# MiniCar.net
KiCad netlist of a schematic drawn in Altium Designer
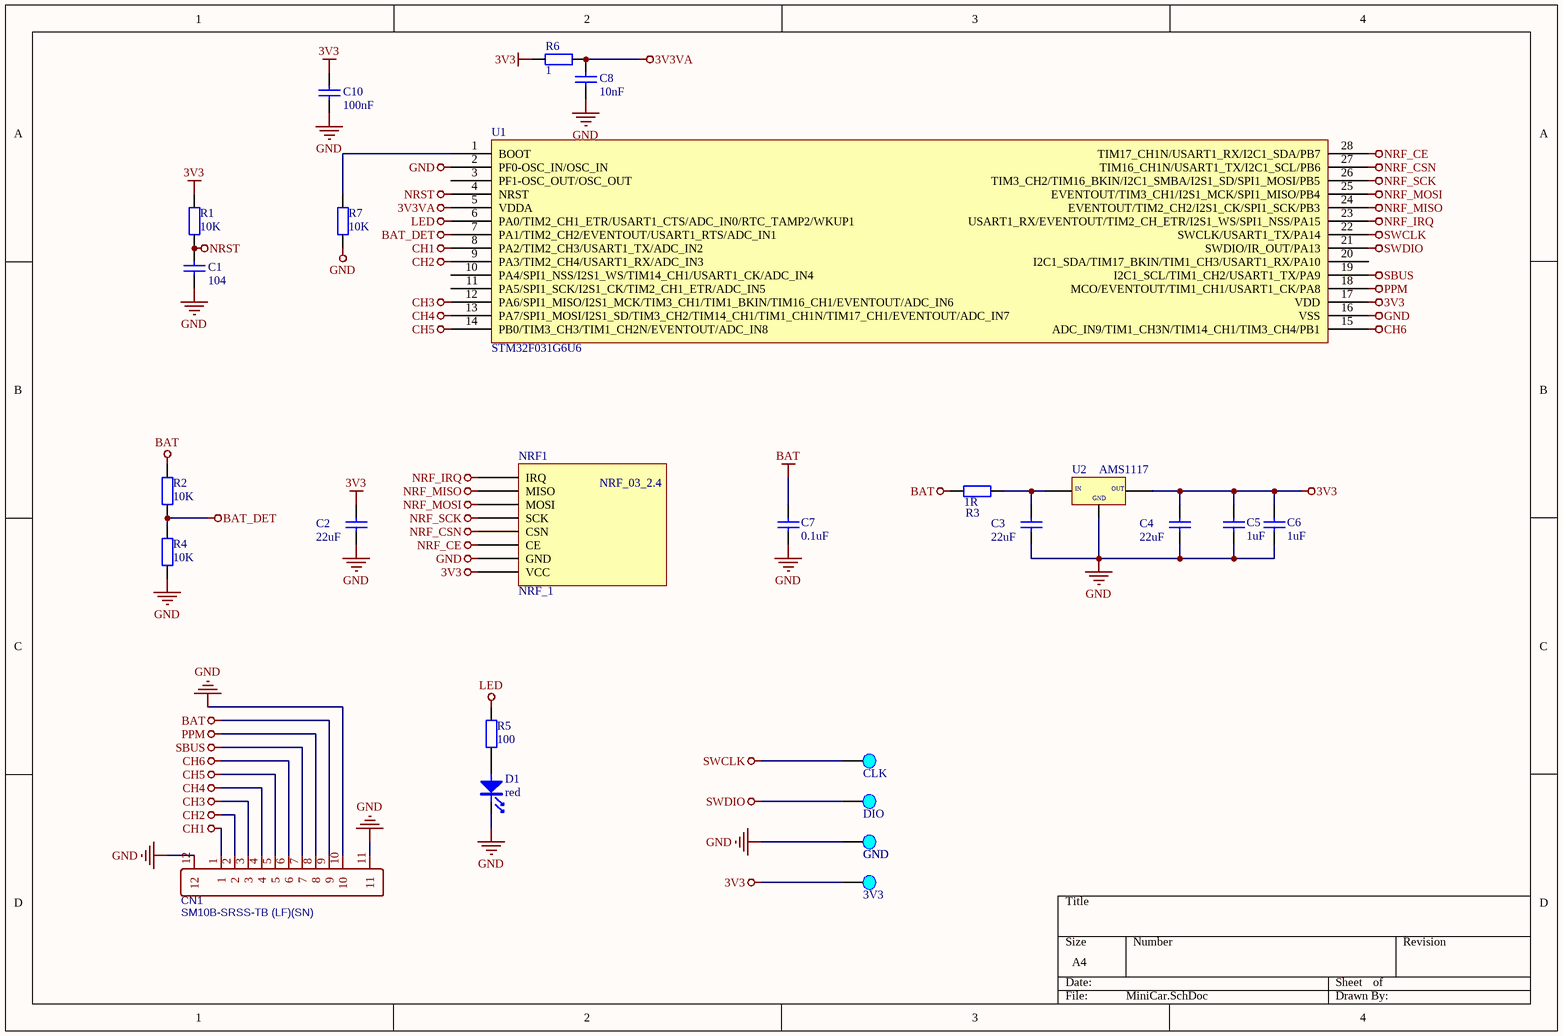
[diagram p0: MiniCar.SchDoc]

(export (version "E")
  (design (tool "Eeschema 10.0.6"))
  (components
    (comp (ref "3V3")
      (value "3V3")
      (footprint "Pad_B")
      (fields (field (name "_REMARKS") "3V3"))
      (libsource (lib "元件库") (part "Pad"))
    )
    (comp (ref "C1")
      (value "104")
      (footprint "电容_C0603")
      (fields (field (name "C") "104"))
      (libsource (lib "元件库") (part "cap"))
    )
    (comp (ref "C2")
      (value "22uF")
      (footprint "电容_C1206")
      (fields (field (name "C") "22uF"))
      (libsource (lib "元件库") (part "cap"))
    )
    (comp (ref "C3")
      (value "22uF")
      (footprint "电容_C1206")
      (fields (field (name "C") "22uF"))
      (libsource (lib "元件库") (part "cap"))
    )
    (comp (ref "C4")
      (value "22uF")
      (footprint "电容_C1206")
      (fields (field (name "C") "22uF"))
      (libsource (lib "元件库") (part "cap"))
    )
    (comp (ref "C5")
      (value "1uF")
      (footprint "电容_C0603")
      (fields (field (name "C") "1uF"))
      (libsource (lib "元件库") (part "cap"))
    )
    (comp (ref "C6")
      (value "1uF")
      (footprint "电容_C0603")
      (fields (field (name "C") "1uF"))
      (libsource (lib "元件库") (part "cap"))
    )
    (comp (ref "C7")
      (value "0.1uF")
      (footprint "电容_C0603")
      (fields (field (name "C") "0.1uF"))
      (libsource (lib "元件库") (part "cap"))
    )
    (comp (ref "C8")
      (value "10nF")
      (footprint "电容_C0603")
      (fields (field (name "C") "10nF"))
      (libsource (lib "元件库") (part "cap"))
    )
    (comp (ref "C10")
      (value "100nF")
      (footprint "电容_C0603")
      (fields (field (name "C") "100nF"))
      (libsource (lib "元件库") (part "cap"))
    )
    (comp (ref "CLK")
      (value "CLK")
      (footprint "Pad_B")
      (fields (field (name "_REMARKS") "CLK"))
      (libsource (lib "元件库") (part "Pad"))
    )
    (comp (ref "CN1")
      (value "SM10B-SRSS-TB (LF)(SN)")
      (footprint "CONN-SMD_10P-P1.00_SM10B-SRSS-TB(LF)(SN)")
      (fields (field (name "BOM_SUPPLIER PART") "C160409") (field (name "CONTRIBUTOR") "LCSC"))
      (libsource (lib "Dj140") (part "SM10B-SRSS-TB (LF)(SN)"))
    )
    (comp (ref "D1") (value "red") (footprint "LED_0603") (libsource (lib "元件库") (part "LED")))
    (comp (ref "DIO")
      (value "DIO")
      (footprint "Pad_B")
      (fields (field (name "_REMARKS") "DIO"))
      (libsource (lib "元件库") (part "Pad"))
    )
    (comp (ref "GND")
      (value "GND")
      (footprint "Pad_B")
      (fields (field (name "_REMARKS") "GND"))
      (libsource (lib "元件库") (part "Pad"))
    )
    (comp (ref "NRF1") (value "NRF_1") (footprint "NRF-1") (libsource (lib "Schlib1") (part "NRF_1")))
    (comp (ref "R1")
      (value "10K")
      (footprint "电阻_R0603")
      (fields (field (name "R") "10K"))
      (libsource (lib "") (part "Res_1"))
    )
    (comp (ref "R2")
      (value "10K")
      (footprint "电阻_R0603")
      (fields (field (name "R") "10K"))
      (libsource (lib "") (part "Res_1"))
    )
    (comp (ref "R3")
      (value "1R")
      (footprint "电阻_R0603")
      (fields (field (name "R") "1R"))
      (libsource (lib "") (part "Res_3"))
    )
    (comp (ref "R4")
      (value "10K")
      (footprint "电阻_R0603")
      (fields (field (name "R") "10K"))
      (libsource (lib "") (part "Res_1"))
    )
    (comp (ref "R5")
      (value "100")
      (footprint "电阻_R0603")
      (fields (field (name "R") "100"))
      (libsource (lib "") (part "Res_2"))
    )
    (comp (ref "R6")
      (value "1")
      (footprint "电阻_R0603")
      (fields (field (name "R") "1"))
      (libsource (lib "元件库") (part "Res"))
    )
    (comp (ref "R7")
      (value "10K")
      (footprint "电阻_R0603")
      (fields (field (name "R") "10K"))
      (libsource (lib "") (part "Res_2"))
    )
    (comp (ref "U1")
      (value "STM32F031G6U6")
      (footprint "ST主控_UFQFPN28")
      (libsource (lib "元件库") (part "STM32F031G6U6"))
    )
    (comp (ref "U2") (value "AMS1117") (footprint "稳压芯片_SOT-89") (libsource (lib "元件库") (part "AMS1117")))
  )
  (nets
    (net (code "1") (name "3V3") (class "Default")
      (node (ref "3V3") (pin "1") (pinfunction "*_1") (pintype "passive"))
      (node (ref "C10") (pin "2") (pinfunction "2_2") (pintype "passive"))
      (node (ref "C2") (pin "2") (pinfunction "2_2") (pintype "passive"))
      (node (ref "C4") (pin "2") (pinfunction "2_2") (pintype "passive"))
      (node (ref "C5") (pin "2") (pinfunction "2_2") (pintype "passive"))
      (node (ref "C6") (pin "2") (pinfunction "2_2") (pintype "passive"))
      (node (ref "NRF1") (pin "1") (pinfunction "VCC_1") (pintype "passive"))
      (node (ref "R1") (pin "2") (pinfunction "2_2") (pintype "passive"))
      (node (ref "R6") (pin "2") (pinfunction "2_2") (pintype "passive"))
      (node (ref "U1") (pin "17") (pinfunction "VDD_17") (pintype "passive"))
      (node (ref "U2") (pin "2") (pinfunction "OUT_2") (pintype "passive"))
    )
    (net (code "2") (name "3V3VA") (class "Default")
      (node (ref "C8") (pin "2") (pinfunction "2_2") (pintype "passive"))
      (node (ref "R6") (pin "1") (pinfunction "1_1") (pintype "passive"))
      (node (ref "U1") (pin "5") (pinfunction "VDDA_5") (pintype "passive"))
    )
    (net (code "3") (name "BAT") (class "Default")
      (node (ref "C7") (pin "1") (pinfunction "1_1") (pintype "passive"))
      (node (ref "CN1") (pin "9") (pinfunction "9_9") (pintype "passive"))
      (node (ref "R2") (pin "2") (pinfunction "2_2") (pintype "passive"))
      (node (ref "R3") (pin "1") (pinfunction "1_1") (pintype "passive"))
    )
    (net (code "4") (name "BAT_DET") (class "Default")
      (node (ref "R2") (pin "1") (pinfunction "1_1") (pintype "passive"))
      (node (ref "R4") (pin "2") (pinfunction "2_2") (pintype "passive"))
      (node (ref "U1") (pin "7") (pinfunction "PA1/TIM2_CH2/EVENTOUT/USART1_RTS/ADC_IN1_7") (pintype "passive"))
    )
    (net (code "5") (name "CH1") (class "Default")
      (node (ref "CN1") (pin "1") (pinfunction "1_1") (pintype "passive"))
      (node (ref "U1") (pin "8") (pinfunction "PA2/TIM2_CH3/USART1_TX/ADC_IN2_8") (pintype "passive"))
    )
    (net (code "6") (name "CH2") (class "Default")
      (node (ref "CN1") (pin "2") (pinfunction "2_2") (pintype "passive"))
      (node (ref "U1") (pin "9") (pinfunction "PA3/TIM2_CH4/USART1_RX/ADC_IN3_9") (pintype "passive"))
    )
    (net (code "7") (name "CH3") (class "Default")
      (node (ref "CN1") (pin "3") (pinfunction "3_3") (pintype "passive"))
      (node (ref "U1") (pin "12") (pinfunction "PA6/SPI1_MISO/I2S1_MCK/TIM3_CH1/TIM1_BKIN/TIM16_CH1/EVENTOUT/ADC_IN6_12") (pintype "passive"))
    )
    (net (code "8") (name "CH4") (class "Default")
      (node (ref "CN1") (pin "4") (pinfunction "4_4") (pintype "passive"))
      (node (ref "U1") (pin "13") (pinfunction "PA7/SPI1_MOSI/I2S1_SD/TIM3_CH2/TIM14_CH1/TIM1_CH1N/TIM17_CH1/EVENTOUT/ADC_IN7_13") (pintype "passive"))
    )
    (net (code "9") (name "CH5") (class "Default")
      (node (ref "CN1") (pin "5") (pinfunction "5_5") (pintype "passive"))
      (node (ref "U1") (pin "14") (pinfunction "PB0/TIM3_CH3/TIM1_CH2N/EVENTOUT/ADC_IN8_14") (pintype "passive"))
    )
    (net (code "10") (name "CH6") (class "Default")
      (node (ref "CN1") (pin "6") (pinfunction "6_6") (pintype "passive"))
      (node (ref "U1") (pin "15") (pinfunction "ADC_IN9/TIM1_CH3N/TIM14_CH1/TIM3_CH4/PB1_15") (pintype "passive"))
    )
    (net (code "11") (name "GND") (class "Default")
      (node (ref "C1") (pin "1") (pinfunction "1_1") (pintype "passive"))
      (node (ref "C10") (pin "1") (pinfunction "1_1") (pintype "passive"))
      (node (ref "C2") (pin "1") (pinfunction "1_1") (pintype "passive"))
      (node (ref "C3") (pin "1") (pinfunction "1_1") (pintype "passive"))
      (node (ref "C4") (pin "1") (pinfunction "1_1") (pintype "passive"))
      (node (ref "C5") (pin "1") (pinfunction "1_1") (pintype "passive"))
      (node (ref "C6") (pin "1") (pinfunction "1_1") (pintype "passive"))
      (node (ref "C7") (pin "2") (pinfunction "2_2") (pintype "passive"))
      (node (ref "C8") (pin "1") (pinfunction "1_1") (pintype "passive"))
      (node (ref "CN1") (pin "10") (pinfunction "10_10") (pintype "passive"))
      (node (ref "CN1") (pin "11") (pinfunction "11_11") (pintype "passive"))
      (node (ref "CN1") (pin "12") (pinfunction "12_12") (pintype "passive"))
      (node (ref "D1") (pin "K") (pinfunction "K_K") (pintype "passive"))
      (node (ref "GND") (pin "1") (pinfunction "*_1") (pintype "passive"))
      (node (ref "NRF1") (pin "2") (pinfunction "GND_2") (pintype "passive"))
      (node (ref "R4") (pin "1") (pinfunction "1_1") (pintype "passive"))
      (node (ref "R7") (pin "2") (pinfunction "2_2") (pintype "passive"))
      (node (ref "U1") (pin "16") (pinfunction "VSS_16") (pintype "passive"))
      (node (ref "U1") (pin "2") (pinfunction "PF0-OSC_IN/OSC_IN_2") (pintype "passive"))
      (node (ref "U2") (pin "1") (pinfunction "GND_1") (pintype "passive"))
    )
    (net (code "12") (name "LED") (class "Default")
      (node (ref "R5") (pin "1") (pinfunction "1_1") (pintype "passive"))
      (node (ref "U1") (pin "6") (pinfunction "PA0/TIM2_CH1_ETR/USART1_CTS/ADC_IN0/RTC_TAMP2/WKUP1_6") (pintype "passive"))
    )
    (net (code "13") (name "NRF_CE") (class "Default")
      (node (ref "NRF1") (pin "3") (pinfunction "CE_3") (pintype "passive"))
      (node (ref "U1") (pin "28") (pinfunction "TIM17_CH1N/USART1_RX/I2C1_SDA/PB7_28") (pintype "passive"))
    )
    (net (code "14") (name "NRF_CSN") (class "Default")
      (node (ref "NRF1") (pin "4") (pinfunction "CSN_4") (pintype "passive"))
      (node (ref "U1") (pin "27") (pinfunction "TIM16_CH1N/USART1_TX/I2C1_SCL/PB6_27") (pintype "passive"))
    )
    (net (code "15") (name "NRF_IRQ") (class "Default")
      (node (ref "NRF1") (pin "8") (pinfunction "IRQ_8") (pintype "passive"))
      (node (ref "U1") (pin "23") (pinfunction "USART1_RX/EVENTOUT/TIM2_CH_ETR/I2S1_WS/SPI1_NSS/PA15_23") (pintype "passive"))
    )
    (net (code "16") (name "NRF_MISO") (class "Default")
      (node (ref "NRF1") (pin "7") (pinfunction "MISO_7") (pintype "passive"))
      (node (ref "U1") (pin "24") (pinfunction "EVENTOUT/TIM2_CH2/I2S1_CK/SPI1_SCK/PB3_24") (pintype "passive"))
    )
    (net (code "17") (name "NRF_MOSI") (class "Default")
      (node (ref "NRF1") (pin "6") (pinfunction "MOSI_6") (pintype "passive"))
      (node (ref "U1") (pin "25") (pinfunction "EVENTOUT/TIM3_CH1/I2S1_MCK/SPI1_MISO/PB4_25") (pintype "passive"))
    )
    (net (code "18") (name "NRF_SCK") (class "Default")
      (node (ref "NRF1") (pin "5") (pinfunction "SCK_5") (pintype "passive"))
      (node (ref "U1") (pin "26") (pinfunction "TIM3_CH2/TIM16_BKIN/I2C1_SMBA/I2S1_SD/SPI1_MOSI/PB5_26") (pintype "passive"))
    )
    (net (code "19") (name "NRST") (class "Default")
      (node (ref "C1") (pin "2") (pinfunction "2_2") (pintype "passive"))
      (node (ref "R1") (pin "1") (pinfunction "1_1") (pintype "passive"))
      (node (ref "U1") (pin "4") (pinfunction "NRST_4") (pintype "passive"))
    )
    (net (code "20") (name "Net-(D1-PadA)") (class "Default")
      (node (ref "D1") (pin "A") (pinfunction "A_A") (pintype "passive"))
      (node (ref "R5") (pin "2") (pinfunction "2_2") (pintype "passive"))
    )
    (net (code "21") (name "Net-(U1-BOOT)") (class "Default")
      (node (ref "R7") (pin "1") (pinfunction "1_1") (pintype "passive"))
      (node (ref "U1") (pin "1") (pinfunction "BOOT_1") (pintype "passive"))
    )
    (net (code "22") (name "Net-(U2-VIN)") (class "Default")
      (node (ref "C3") (pin "2") (pinfunction "2_2") (pintype "passive"))
      (node (ref "R3") (pin "2") (pinfunction "2_2") (pintype "passive"))
      (node (ref "U2") (pin "3") (pinfunction "VIN_3") (pintype "passive"))
    )
    (net (code "23") (name "PPM") (class "Default")
      (node (ref "CN1") (pin "8") (pinfunction "8_8") (pintype "passive"))
      (node (ref "U1") (pin "18") (pinfunction "MCO/EVENTOUT/TIM1_CH1/USART1_CK/PA8_18") (pintype "passive"))
    )
    (net (code "24") (name "SBUS") (class "Default")
      (node (ref "CN1") (pin "7") (pinfunction "7_7") (pintype "passive"))
      (node (ref "U1") (pin "19") (pinfunction "I2C1_SCL/TIM1_CH2/USART1_TX/PA9_19") (pintype "passive"))
    )
    (net (code "25") (name "SWCLK") (class "Default")
      (node (ref "CLK") (pin "1") (pinfunction "*_1") (pintype "passive"))
      (node (ref "U1") (pin "22") (pinfunction "SWCLK/USART1_TX/PA14_22") (pintype "passive"))
    )
    (net (code "26") (name "SWDIO") (class "Default")
      (node (ref "DIO") (pin "1") (pinfunction "*_1") (pintype "passive"))
      (node (ref "U1") (pin "21") (pinfunction "SWDIO/IR_OUT/PA13_21") (pintype "passive"))
    )
    (net (code "27") (name "unconnected-(U1-I2C1_SDA{slash}TIM17_BKIN{slash}TIM1_CH3{slash}USART1_RX{slash}PA10-Pad20)") (class "Default")
      (node (ref "U1") (pin "20") (pinfunction "I2C1_SDA/TIM17_BKIN/TIM1_CH3/USART1_RX/PA10_20") (pintype "passive"))
    )
    (net (code "28") (name "unconnected-(U1-PA4{slash}SPI1_NSS{slash}I2S1_WS{slash}TIM14_CH1{slash}USART1_CK{slash}ADC_IN4-Pad10)") (class "Default")
      (node (ref "U1") (pin "10") (pinfunction "PA4/SPI1_NSS/I2S1_WS/TIM14_CH1/USART1_CK/ADC_IN4_10") (pintype "passive"))
    )
    (net (code "29") (name "unconnected-(U1-PA5{slash}SPI1_SCK{slash}I2S1_CK{slash}TIM2_CH1_ETR{slash}ADC_IN5-Pad11)") (class "Default")
      (node (ref "U1") (pin "11") (pinfunction "PA5/SPI1_SCK/I2S1_CK/TIM2_CH1_ETR/ADC_IN5_11") (pintype "passive"))
    )
    (net (code "30") (name "unconnected-(U1-PF1-OSC_OUT{slash}OSC_OUT-Pad3)") (class "Default")
      (node (ref "U1") (pin "3") (pinfunction "PF1-OSC_OUT/OSC_OUT_3") (pintype "passive"))
    )
  )
)
